# Sensor-platiene.net
KiCad netlist of a schematic drawn in EAGLE
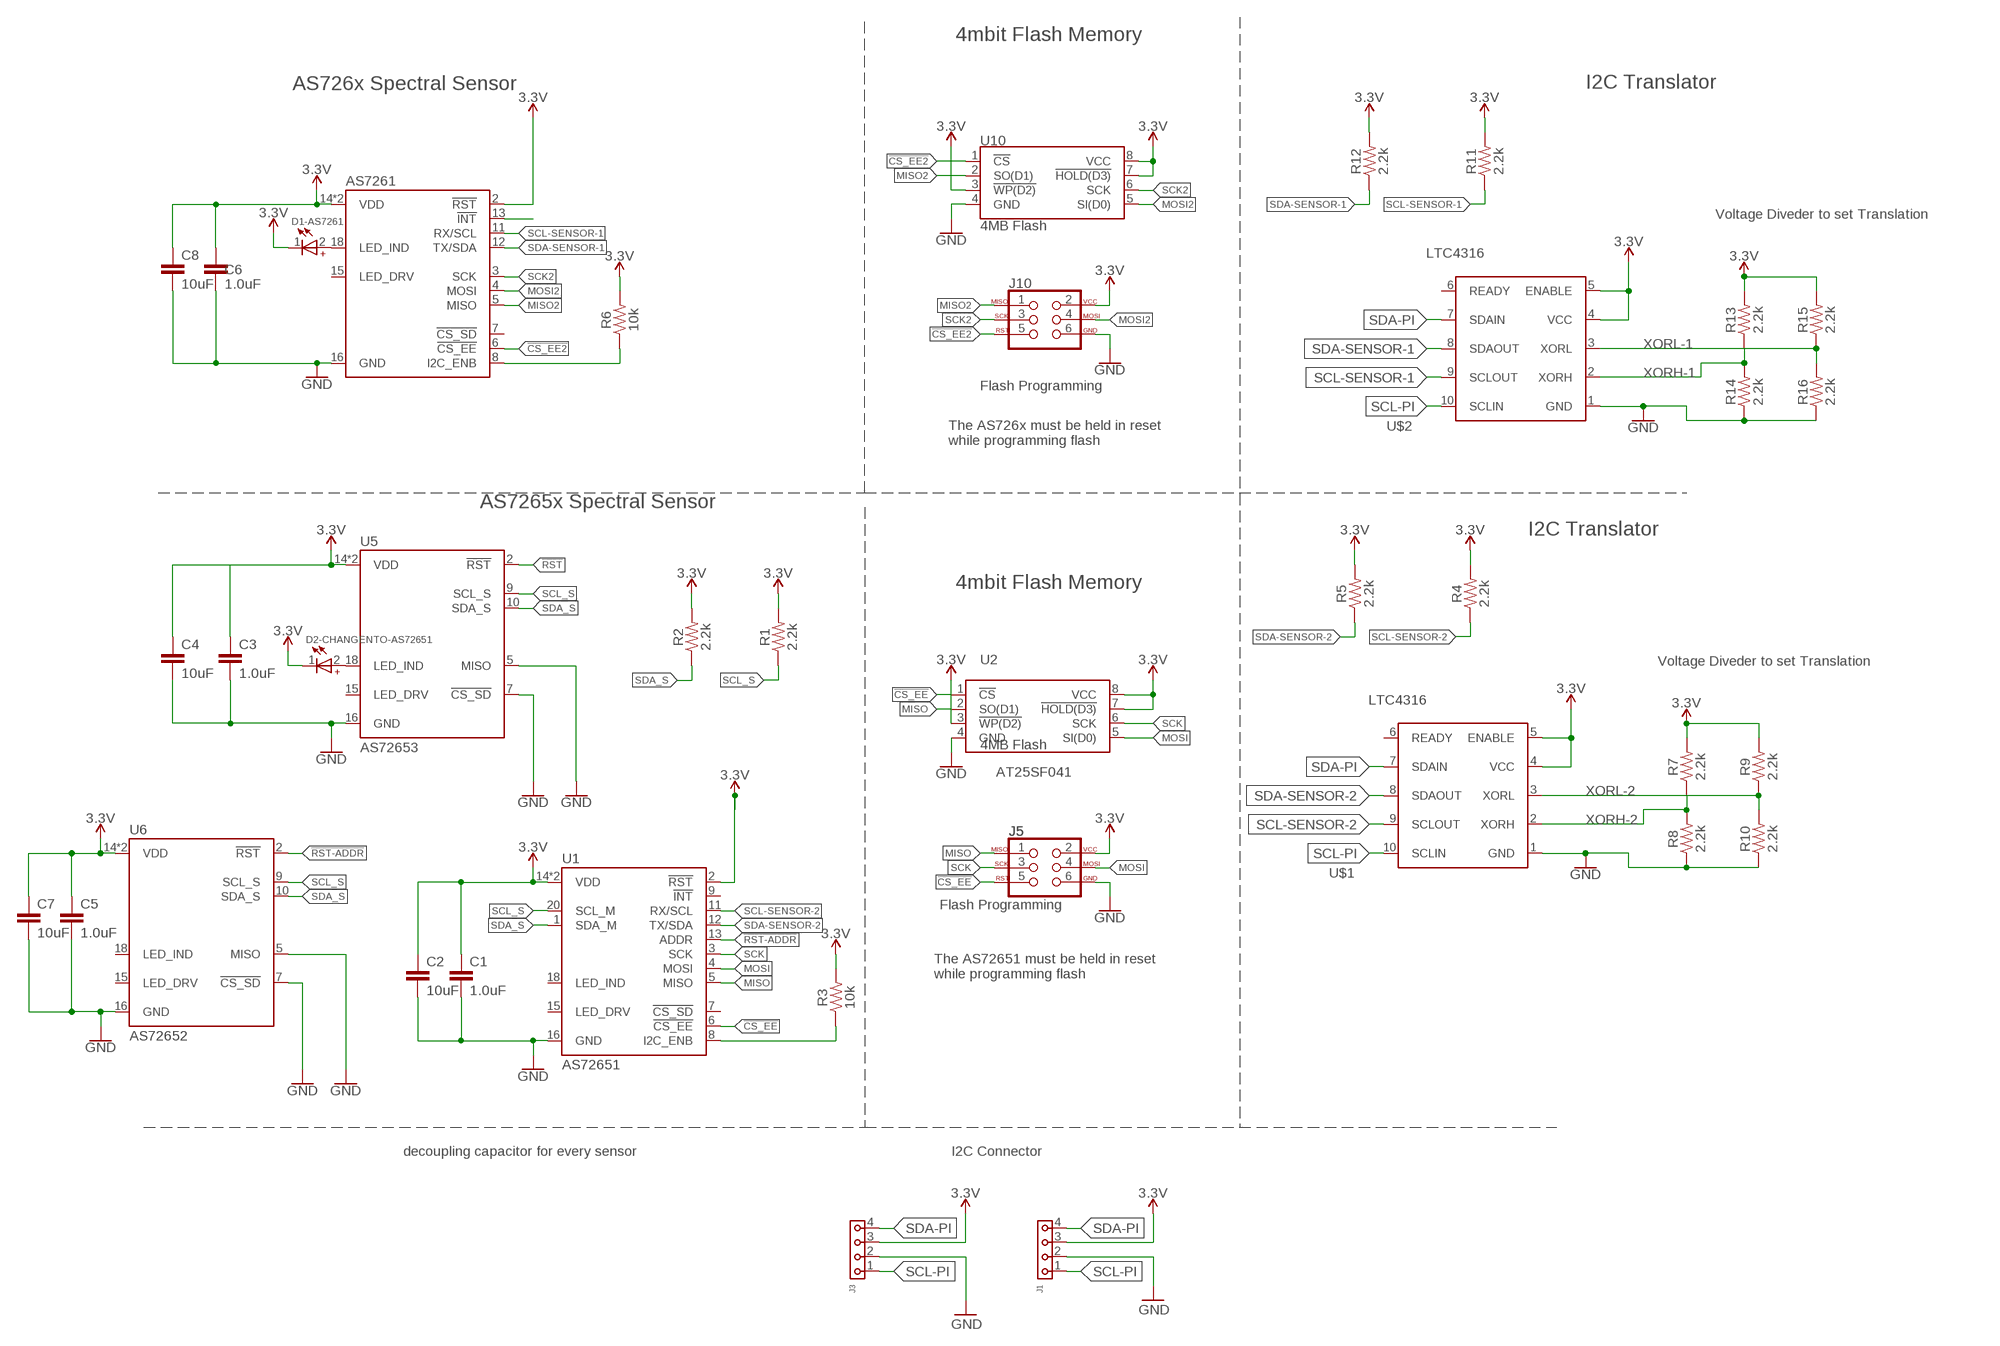
[diagram p0: schematic, sheet 1]

(export (version "E")
  (design (tool "Eeschema 10.0.6"))
  (components
    (comp (ref "AS7261")
      (value "IR")
      (footprint "eagle-import:LGA20")
      (libsource (lib "eagle-import") (part "AS726XIR"))
    )
    (comp (ref "C1")
      (value "1.0uF")
      (footprint "eagle-import:0603")
      (libsource (lib "eagle-import") (part "1.0UF-0603-16V-10%"))
    )
    (comp (ref "C2")
      (value "10uF")
      (footprint "eagle-import:0603")
      (libsource (lib "eagle-import") (part "10UF-0603-6.3V-20%"))
    )
    (comp (ref "C3")
      (value "1.0uF")
      (footprint "eagle-import:0603")
      (libsource (lib "eagle-import") (part "1.0UF-0603-16V-10%"))
    )
    (comp (ref "C4")
      (value "10uF")
      (footprint "eagle-import:0603")
      (libsource (lib "eagle-import") (part "10UF-0603-6.3V-20%"))
    )
    (comp (ref "C5")
      (value "1.0uF")
      (footprint "eagle-import:0603")
      (libsource (lib "eagle-import") (part "1.0UF-0603-16V-10%"))
    )
    (comp (ref "C6")
      (value "1.0uF")
      (footprint "eagle-import:0603")
      (libsource (lib "eagle-import") (part "1.0UF-0603-16V-10%"))
    )
    (comp (ref "C7")
      (value "10uF")
      (footprint "eagle-import:0603")
      (libsource (lib "eagle-import") (part "10UF-0603-6.3V-20%"))
    )
    (comp (ref "C8")
      (value "10uF")
      (footprint "eagle-import:0603")
      (libsource (lib "eagle-import") (part "10UF-0603-6.3V-20%"))
    )
    (comp (ref "D1-AS7261")
      (value "WL-SMCW_1206_150120RS75000")
      (footprint "eagle-import:WL-SMCW_1206")
      (libsource (lib "eagle-import") (part "WL-SMCW_1206_150120RS75000"))
    )
    (comp (ref "D2-CHANGENTO-AS72651")
      (value "WL-SMCW_1206_150120RS75000")
      (footprint "eagle-import:WL-SMCW_1206")
      (libsource (lib "eagle-import") (part "WL-SMCW_1206_150120RS75000"))
    )
    (comp (ref "J1")
      (value "6130XX11821_61300411821")
      (footprint "eagle-import:61300411821")
      (libsource (lib "eagle-import") (part "6130XX11821_61300411821"))
    )
    (comp (ref "J3")
      (value "6130XX11821_61300411821")
      (footprint "eagle-import:61300411821")
      (libsource (lib "eagle-import") (part "6130XX11821_61300411821"))
    )
    (comp (ref "J5")
      (value "Flash Programming")
      (footprint "eagle-import:2X3_TEST_POINTS")
      (libsource (lib "eagle-import") (part "AVR_SPI_PROG_3X2TESTPOINTS"))
    )
    (comp (ref "J10")
      (value "Flash Programming")
      (footprint "eagle-import:2X3_TEST_POINTS")
      (libsource (lib "eagle-import") (part "AVR_SPI_PROG_3X2TESTPOINTS"))
    )
    (comp (ref "R1")
      (value "2.2k")
      (footprint "eagle-import:0603")
      (libsource (lib "eagle-import") (part "2.2KOHM-0603-1/10W-1%"))
    )
    (comp (ref "R2")
      (value "2.2k")
      (footprint "eagle-import:0603")
      (libsource (lib "eagle-import") (part "2.2KOHM-0603-1/10W-1%"))
    )
    (comp (ref "R3")
      (value "10k")
      (footprint "eagle-import:0603")
      (libsource (lib "eagle-import") (part "10KOHM-0603-1/10W-1%"))
    )
    (comp (ref "R4")
      (value "2.2k")
      (footprint "eagle-import:0603")
      (libsource (lib "eagle-import") (part "2.2KOHM-0603-1/10W-1%"))
    )
    (comp (ref "R5")
      (value "2.2k")
      (footprint "eagle-import:0603")
      (libsource (lib "eagle-import") (part "2.2KOHM-0603-1/10W-1%"))
    )
    (comp (ref "R6")
      (value "10k")
      (footprint "eagle-import:0603")
      (libsource (lib "eagle-import") (part "10KOHM-0603-1/10W-1%"))
    )
    (comp (ref "R7")
      (value "2.2k")
      (footprint "eagle-import:0603")
      (libsource (lib "eagle-import") (part "2.2KOHM-0603-1/10W-1%"))
    )
    (comp (ref "R8")
      (value "2.2k")
      (footprint "eagle-import:0603")
      (libsource (lib "eagle-import") (part "2.2KOHM-0603-1/10W-1%"))
    )
    (comp (ref "R9")
      (value "2.2k")
      (footprint "eagle-import:0603")
      (libsource (lib "eagle-import") (part "2.2KOHM-0603-1/10W-1%"))
    )
    (comp (ref "R10")
      (value "2.2k")
      (footprint "eagle-import:0603")
      (libsource (lib "eagle-import") (part "2.2KOHM-0603-1/10W-1%"))
    )
    (comp (ref "R11")
      (value "2.2k")
      (footprint "eagle-import:0603")
      (libsource (lib "eagle-import") (part "2.2KOHM-0603-1/10W-1%"))
    )
    (comp (ref "R12")
      (value "2.2k")
      (footprint "eagle-import:0603")
      (libsource (lib "eagle-import") (part "2.2KOHM-0603-1/10W-1%"))
    )
    (comp (ref "R13")
      (value "2.2k")
      (footprint "eagle-import:0603")
      (libsource (lib "eagle-import") (part "2.2KOHM-0603-1/10W-1%"))
    )
    (comp (ref "R14")
      (value "2.2k")
      (footprint "eagle-import:0603")
      (libsource (lib "eagle-import") (part "2.2KOHM-0603-1/10W-1%"))
    )
    (comp (ref "R15")
      (value "2.2k")
      (footprint "eagle-import:0603")
      (libsource (lib "eagle-import") (part "2.2KOHM-0603-1/10W-1%"))
    )
    (comp (ref "R16")
      (value "2.2k")
      (footprint "eagle-import:0603")
      (libsource (lib "eagle-import") (part "2.2KOHM-0603-1/10W-1%"))
    )
    (comp (ref "U$1")
      (value "LTC4316")
      (footprint "eagle-import:MS-PACKAGE")
      (libsource (lib "eagle-import") (part "LTC4316"))
    )
    (comp (ref "U$2")
      (value "LTC4316")
      (footprint "eagle-import:MS-PACKAGE")
      (libsource (lib "eagle-import") (part "LTC4316"))
    )
    (comp (ref "U1")
      (value "AS72651")
      (footprint "eagle-import:LGA20")
      (libsource (lib "eagle-import") (part "AS72651"))
    )
    (comp (ref "U2")
      (value "4MB Flash")
      (footprint "eagle-import:SO08")
      (libsource (lib "eagle-import") (part "AT25SF041"))
    )
    (comp (ref "U5")
      (value "AS72653")
      (footprint "eagle-import:LGA20")
      (libsource (lib "eagle-import") (part "AS72653"))
    )
    (comp (ref "U6")
      (value "AS72652")
      (footprint "eagle-import:LGA20")
      (libsource (lib "eagle-import") (part "AS72652"))
    )
    (comp (ref "U10")
      (value "4MB Flash")
      (footprint "eagle-import:SO08")
      (libsource (lib "eagle-import") (part "AT25SF041"))
    )
  )
  (nets
    (net (code "1") (name "/XORH-1") (class "Default")
      (node (ref "R13") (pin "1") (pinfunction "1_1") (pintype "passive"))
      (node (ref "R14") (pin "2") (pinfunction "2_2") (pintype "passive"))
      (node (ref "U$2") (pin "2") (pinfunction "XORH_2") (pintype "bidirectional"))
    )
    (net (code "2") (name "/XORH-2") (class "Default")
      (node (ref "R7") (pin "1") (pinfunction "1_1") (pintype "passive"))
      (node (ref "R8") (pin "2") (pinfunction "2_2") (pintype "passive"))
      (node (ref "U$1") (pin "2") (pinfunction "XORH_2") (pintype "bidirectional"))
    )
    (net (code "3") (name "/XORL-1") (class "Default")
      (node (ref "R15") (pin "1") (pinfunction "1_1") (pintype "passive"))
      (node (ref "R16") (pin "2") (pinfunction "2_2") (pintype "passive"))
      (node (ref "U$2") (pin "3") (pinfunction "XORL_3") (pintype "bidirectional"))
    )
    (net (code "4") (name "/XORL-2") (class "Default")
      (node (ref "R10") (pin "2") (pinfunction "2_2") (pintype "passive"))
      (node (ref "R9") (pin "1") (pinfunction "1_1") (pintype "passive"))
      (node (ref "U$1") (pin "3") (pinfunction "XORL_3") (pintype "bidirectional"))
    )
    (net (code "5") (name "/~{CS_EE2}") (class "Default")
      (node (ref "AS7261") (pin "6") (pinfunction "~{CS_EE}_6") (pintype "bidirectional"))
      (node (ref "J10") (pin "5") (pinfunction "5_5") (pintype "passive"))
      (node (ref "U10") (pin "1") (pinfunction "~{CS}_1") (pintype "bidirectional"))
    )
    (net (code "6") (name "/~{CS_EE}") (class "Default")
      (node (ref "J5") (pin "5") (pinfunction "5_5") (pintype "passive"))
      (node (ref "U1") (pin "6") (pinfunction "~{CS_EE}_6") (pintype "bidirectional"))
      (node (ref "U2") (pin "1") (pinfunction "~{CS}_1") (pintype "bidirectional"))
    )
    (net (code "7") (name "/~{RST-ADDR}") (class "Default")
      (node (ref "U1") (pin "13") (pinfunction "ADDR_13") (pintype "bidirectional"))
      (node (ref "U6") (pin "2") (pinfunction "~{RST}_2") (pintype "bidirectional"))
    )
    (net (code "8") (name "/~{RST}") (class "Default")
      (node (ref "U5") (pin "2") (pinfunction "~{RST}_2") (pintype "bidirectional"))
    )
    (net (code "9") (name "3.3V") (class "Default")
      (node (ref "AS7261") (pin "14") (pinfunction "VDD_14") (pintype "bidirectional"))
      (node (ref "AS7261") (pin "17") (pinfunction "VDD_17") (pintype "bidirectional"))
      (node (ref "AS7261") (pin "2") (pinfunction "~{RST}_2") (pintype "bidirectional"))
      (node (ref "C1") (pin "1") (pinfunction "1_1") (pintype "passive"))
      (node (ref "C2") (pin "1") (pinfunction "1_1") (pintype "passive"))
      (node (ref "C3") (pin "1") (pinfunction "1_1") (pintype "passive"))
      (node (ref "C4") (pin "1") (pinfunction "1_1") (pintype "passive"))
      (node (ref "C5") (pin "1") (pinfunction "1_1") (pintype "passive"))
      (node (ref "C6") (pin "1") (pinfunction "1_1") (pintype "passive"))
      (node (ref "C7") (pin "1") (pinfunction "1_1") (pintype "passive"))
      (node (ref "C8") (pin "1") (pinfunction "1_1") (pintype "passive"))
      (node (ref "D1-AS7261") (pin "1") (pinfunction "-_1") (pintype "passive"))
      (node (ref "D2-CHANGENTO-AS72651") (pin "1") (pinfunction "-_1") (pintype "passive"))
      (node (ref "J1") (pin "3") (pinfunction "3_3") (pintype "passive"))
      (node (ref "J10") (pin "2") (pinfunction "2_2") (pintype "passive"))
      (node (ref "J3") (pin "3") (pinfunction "3_3") (pintype "passive"))
      (node (ref "J5") (pin "2") (pinfunction "2_2") (pintype "passive"))
      (node (ref "R1") (pin "2") (pinfunction "2_2") (pintype "passive"))
      (node (ref "R11") (pin "2") (pinfunction "2_2") (pintype "passive"))
      (node (ref "R12") (pin "2") (pinfunction "2_2") (pintype "passive"))
      (node (ref "R13") (pin "2") (pinfunction "2_2") (pintype "passive"))
      (node (ref "R15") (pin "2") (pinfunction "2_2") (pintype "passive"))
      (node (ref "R2") (pin "2") (pinfunction "2_2") (pintype "passive"))
      (node (ref "R3") (pin "2") (pinfunction "2_2") (pintype "passive"))
      (node (ref "R4") (pin "2") (pinfunction "2_2") (pintype "passive"))
      (node (ref "R5") (pin "2") (pinfunction "2_2") (pintype "passive"))
      (node (ref "R6") (pin "2") (pinfunction "2_2") (pintype "passive"))
      (node (ref "R7") (pin "2") (pinfunction "2_2") (pintype "passive"))
      (node (ref "R9") (pin "2") (pinfunction "2_2") (pintype "passive"))
      (node (ref "U$1") (pin "4") (pinfunction "VCC_4") (pintype "bidirectional"))
      (node (ref "U$1") (pin "5") (pinfunction "ENABLE_5") (pintype "bidirectional"))
      (node (ref "U$2") (pin "4") (pinfunction "VCC_4") (pintype "bidirectional"))
      (node (ref "U$2") (pin "5") (pinfunction "ENABLE_5") (pintype "bidirectional"))
      (node (ref "U1") (pin "14") (pinfunction "VDD_14") (pintype "bidirectional"))
      (node (ref "U1") (pin "17") (pinfunction "VDD_17") (pintype "bidirectional"))
      (node (ref "U1") (pin "2") (pinfunction "~{RST}_2") (pintype "bidirectional"))
      (node (ref "U10") (pin "3") (pinfunction "~{WP(D2})_3") (pintype "bidirectional"))
      (node (ref "U10") (pin "7") (pinfunction "~{HOLD(D3})_7") (pintype "bidirectional"))
      (node (ref "U10") (pin "8") (pinfunction "VCC_8") (pintype "bidirectional"))
      (node (ref "U2") (pin "3") (pinfunction "~{WP(D2})_3") (pintype "bidirectional"))
      (node (ref "U2") (pin "7") (pinfunction "~{HOLD(D3})_7") (pintype "bidirectional"))
      (node (ref "U2") (pin "8") (pinfunction "VCC_8") (pintype "bidirectional"))
      (node (ref "U5") (pin "14") (pinfunction "VDD_14") (pintype "bidirectional"))
      (node (ref "U5") (pin "17") (pinfunction "VDD_17") (pintype "bidirectional"))
      (node (ref "U6") (pin "14") (pinfunction "VDD_14") (pintype "bidirectional"))
      (node (ref "U6") (pin "17") (pinfunction "VDD_17") (pintype "bidirectional"))
    )
    (net (code "10") (name "GND") (class "Default")
      (node (ref "AS7261") (pin "16") (pinfunction "GND_16") (pintype "bidirectional"))
      (node (ref "C1") (pin "2") (pinfunction "2_2") (pintype "passive"))
      (node (ref "C2") (pin "2") (pinfunction "2_2") (pintype "passive"))
      (node (ref "C3") (pin "2") (pinfunction "2_2") (pintype "passive"))
      (node (ref "C4") (pin "2") (pinfunction "2_2") (pintype "passive"))
      (node (ref "C5") (pin "2") (pinfunction "2_2") (pintype "passive"))
      (node (ref "C6") (pin "2") (pinfunction "2_2") (pintype "passive"))
      (node (ref "C7") (pin "2") (pinfunction "2_2") (pintype "passive"))
      (node (ref "C8") (pin "2") (pinfunction "2_2") (pintype "passive"))
      (node (ref "J1") (pin "2") (pinfunction "2_2") (pintype "passive"))
      (node (ref "J10") (pin "6") (pinfunction "6_6") (pintype "passive"))
      (node (ref "J3") (pin "2") (pinfunction "2_2") (pintype "passive"))
      (node (ref "J5") (pin "6") (pinfunction "6_6") (pintype "passive"))
      (node (ref "R10") (pin "1") (pinfunction "1_1") (pintype "passive"))
      (node (ref "R14") (pin "1") (pinfunction "1_1") (pintype "passive"))
      (node (ref "R16") (pin "1") (pinfunction "1_1") (pintype "passive"))
      (node (ref "R8") (pin "1") (pinfunction "1_1") (pintype "passive"))
      (node (ref "U$1") (pin "1") (pinfunction "GND_1") (pintype "bidirectional"))
      (node (ref "U$2") (pin "1") (pinfunction "GND_1") (pintype "bidirectional"))
      (node (ref "U1") (pin "16") (pinfunction "GND_16") (pintype "bidirectional"))
      (node (ref "U10") (pin "4") (pinfunction "GND_4") (pintype "bidirectional"))
      (node (ref "U2") (pin "4") (pinfunction "GND_4") (pintype "bidirectional"))
      (node (ref "U5") (pin "16") (pinfunction "GND_16") (pintype "bidirectional"))
      (node (ref "U5") (pin "5") (pinfunction "MISO_5") (pintype "bidirectional"))
      (node (ref "U5") (pin "7") (pinfunction "~{CS_SD}_7") (pintype "bidirectional"))
      (node (ref "U6") (pin "16") (pinfunction "GND_16") (pintype "bidirectional"))
      (node (ref "U6") (pin "5") (pinfunction "MISO_5") (pintype "bidirectional"))
      (node (ref "U6") (pin "7") (pinfunction "~{CS_SD}_7") (pintype "bidirectional"))
    )
    (net (code "11") (name "MISO") (class "Default")
      (node (ref "J5") (pin "1") (pinfunction "1_1") (pintype "passive"))
      (node (ref "U1") (pin "5") (pinfunction "MISO_5") (pintype "bidirectional"))
      (node (ref "U2") (pin "2") (pinfunction "SO(D1)_2") (pintype "bidirectional"))
    )
    (net (code "12") (name "MISO2") (class "Default")
      (node (ref "AS7261") (pin "5") (pinfunction "MISO_5") (pintype "bidirectional"))
      (node (ref "J10") (pin "1") (pinfunction "1_1") (pintype "passive"))
      (node (ref "U10") (pin "2") (pinfunction "SO(D1)_2") (pintype "bidirectional"))
    )
    (net (code "13") (name "MOSI") (class "Default")
      (node (ref "J5") (pin "4") (pinfunction "4_4") (pintype "passive"))
      (node (ref "U1") (pin "4") (pinfunction "MOSI_4") (pintype "bidirectional"))
      (node (ref "U2") (pin "5") (pinfunction "SI(D0)_5") (pintype "bidirectional"))
    )
    (net (code "14") (name "MOSI2") (class "Default")
      (node (ref "AS7261") (pin "4") (pinfunction "MOSI_4") (pintype "bidirectional"))
      (node (ref "J10") (pin "4") (pinfunction "4_4") (pintype "passive"))
      (node (ref "U10") (pin "5") (pinfunction "SI(D0)_5") (pintype "bidirectional"))
    )
    (net (code "15") (name "Net-(AS7261-I2C_ENB)") (class "Default")
      (node (ref "AS7261") (pin "8") (pinfunction "I2C_ENB_8") (pintype "bidirectional"))
      (node (ref "R6") (pin "1") (pinfunction "1_1") (pintype "passive"))
    )
    (net (code "16") (name "Net-(AS7261-LED_IND)") (class "Default")
      (node (ref "AS7261") (pin "18") (pinfunction "LED_IND_18") (pintype "bidirectional"))
      (node (ref "D1-AS7261") (pin "2") (pinfunction "+_2") (pintype "passive"))
    )
    (net (code "17") (name "Net-(D2-CHANGENTO-AS72651-+)") (class "Default")
      (node (ref "D2-CHANGENTO-AS72651") (pin "2") (pinfunction "+_2") (pintype "passive"))
      (node (ref "U5") (pin "18") (pinfunction "LED_IND_18") (pintype "bidirectional"))
    )
    (net (code "18") (name "Net-(U1-I2C_ENB)") (class "Default")
      (node (ref "R3") (pin "1") (pinfunction "1_1") (pintype "passive"))
      (node (ref "U1") (pin "8") (pinfunction "I2C_ENB_8") (pintype "bidirectional"))
    )
    (net (code "19") (name "SCK") (class "Default")
      (node (ref "J5") (pin "3") (pinfunction "3_3") (pintype "passive"))
      (node (ref "U1") (pin "3") (pinfunction "SCK_3") (pintype "bidirectional"))
      (node (ref "U2") (pin "6") (pinfunction "SCK_6") (pintype "bidirectional"))
    )
    (net (code "20") (name "SCK2") (class "Default")
      (node (ref "AS7261") (pin "3") (pinfunction "SCK_3") (pintype "bidirectional"))
      (node (ref "J10") (pin "3") (pinfunction "3_3") (pintype "passive"))
      (node (ref "U10") (pin "6") (pinfunction "SCK_6") (pintype "bidirectional"))
    )
    (net (code "21") (name "SCL-PI") (class "Default")
      (node (ref "J1") (pin "1") (pinfunction "1_1") (pintype "passive"))
      (node (ref "J3") (pin "1") (pinfunction "1_1") (pintype "passive"))
      (node (ref "U$1") (pin "10") (pinfunction "SCLIN_10") (pintype "bidirectional"))
      (node (ref "U$2") (pin "10") (pinfunction "SCLIN_10") (pintype "bidirectional"))
    )
    (net (code "22") (name "SCL-SENSOR-1") (class "Default")
      (node (ref "AS7261") (pin "11") (pinfunction "RX/SCL_11") (pintype "bidirectional"))
      (node (ref "R11") (pin "1") (pinfunction "1_1") (pintype "passive"))
      (node (ref "U$2") (pin "9") (pinfunction "SCLOUT_9") (pintype "bidirectional"))
    )
    (net (code "23") (name "SCL-SENSOR-2") (class "Default")
      (node (ref "R4") (pin "1") (pinfunction "1_1") (pintype "passive"))
      (node (ref "U$1") (pin "9") (pinfunction "SCLOUT_9") (pintype "bidirectional"))
      (node (ref "U1") (pin "11") (pinfunction "RX/SCL_11") (pintype "bidirectional"))
    )
    (net (code "24") (name "SCL_S") (class "Default")
      (node (ref "R1") (pin "1") (pinfunction "1_1") (pintype "passive"))
      (node (ref "U1") (pin "20") (pinfunction "SCL_M_20") (pintype "bidirectional"))
      (node (ref "U5") (pin "9") (pinfunction "SCL_S_9") (pintype "bidirectional"))
      (node (ref "U6") (pin "9") (pinfunction "SCL_S_9") (pintype "bidirectional"))
    )
    (net (code "25") (name "SDA-PI") (class "Default")
      (node (ref "J1") (pin "4") (pinfunction "4_4") (pintype "passive"))
      (node (ref "J3") (pin "4") (pinfunction "4_4") (pintype "passive"))
      (node (ref "U$1") (pin "7") (pinfunction "SDAIN_7") (pintype "bidirectional"))
      (node (ref "U$2") (pin "7") (pinfunction "SDAIN_7") (pintype "bidirectional"))
    )
    (net (code "26") (name "SDA-SENSOR-1") (class "Default")
      (node (ref "AS7261") (pin "12") (pinfunction "TX/SDA_12") (pintype "bidirectional"))
      (node (ref "R12") (pin "1") (pinfunction "1_1") (pintype "passive"))
      (node (ref "U$2") (pin "8") (pinfunction "SDAOUT_8") (pintype "bidirectional"))
    )
    (net (code "27") (name "SDA-SENSOR-2") (class "Default")
      (node (ref "R5") (pin "1") (pinfunction "1_1") (pintype "passive"))
      (node (ref "U$1") (pin "8") (pinfunction "SDAOUT_8") (pintype "bidirectional"))
      (node (ref "U1") (pin "12") (pinfunction "TX/SDA_12") (pintype "bidirectional"))
    )
    (net (code "28") (name "SDA_S") (class "Default")
      (node (ref "R2") (pin "1") (pinfunction "1_1") (pintype "passive"))
      (node (ref "U1") (pin "1") (pinfunction "SDA_M_1") (pintype "bidirectional"))
      (node (ref "U5") (pin "10") (pinfunction "SDA_S_10") (pintype "bidirectional"))
      (node (ref "U6") (pin "10") (pinfunction "SDA_S_10") (pintype "bidirectional"))
    )
    (net (code "29") (name "unconnected-(AS7261-LED_DRV-Pad15)") (class "Default")
      (node (ref "AS7261") (pin "15") (pinfunction "LED_DRV_15") (pintype "bidirectional"))
    )
    (net (code "30") (name "unconnected-(AS7261-~{CS_SD}-Pad7)") (class "Default")
      (node (ref "AS7261") (pin "7") (pinfunction "~{CS_SD}_7") (pintype "bidirectional"))
    )
    (net (code "31") (name "unconnected-(AS7261-~{INT}-Pad13)") (class "Default")
      (node (ref "AS7261") (pin "13") (pinfunction "~{INT}_13") (pintype "bidirectional"))
    )
    (net (code "32") (name "unconnected-(U$1-READY-Pad6)") (class "Default")
      (node (ref "U$1") (pin "6") (pinfunction "READY_6") (pintype "bidirectional"))
    )
    (net (code "33") (name "unconnected-(U$2-READY-Pad6)") (class "Default")
      (node (ref "U$2") (pin "6") (pinfunction "READY_6") (pintype "bidirectional"))
    )
    (net (code "34") (name "unconnected-(U1-LED_DRV-Pad15)") (class "Default")
      (node (ref "U1") (pin "15") (pinfunction "LED_DRV_15") (pintype "bidirectional"))
    )
    (net (code "35") (name "unconnected-(U1-LED_IND-Pad18)") (class "Default")
      (node (ref "U1") (pin "18") (pinfunction "LED_IND_18") (pintype "bidirectional"))
    )
    (net (code "36") (name "unconnected-(U1-~{CS_SD}-Pad7)") (class "Default")
      (node (ref "U1") (pin "7") (pinfunction "~{CS_SD}_7") (pintype "bidirectional"))
    )
    (net (code "37") (name "unconnected-(U1-~{INT}-Pad9)") (class "Default")
      (node (ref "U1") (pin "9") (pinfunction "~{INT}_9") (pintype "bidirectional"))
    )
    (net (code "38") (name "unconnected-(U5-LED_DRV-Pad15)") (class "Default")
      (node (ref "U5") (pin "15") (pinfunction "LED_DRV_15") (pintype "bidirectional"))
    )
    (net (code "39") (name "unconnected-(U6-LED_DRV-Pad15)") (class "Default")
      (node (ref "U6") (pin "15") (pinfunction "LED_DRV_15") (pintype "bidirectional"))
    )
    (net (code "40") (name "unconnected-(U6-LED_IND-Pad18)") (class "Default")
      (node (ref "U6") (pin "18") (pinfunction "LED_IND_18") (pintype "bidirectional"))
    )
  )
)
